# bluepill_voltage_reg_pcb.net
KiCad netlist of a schematic drawn in Altium Designer
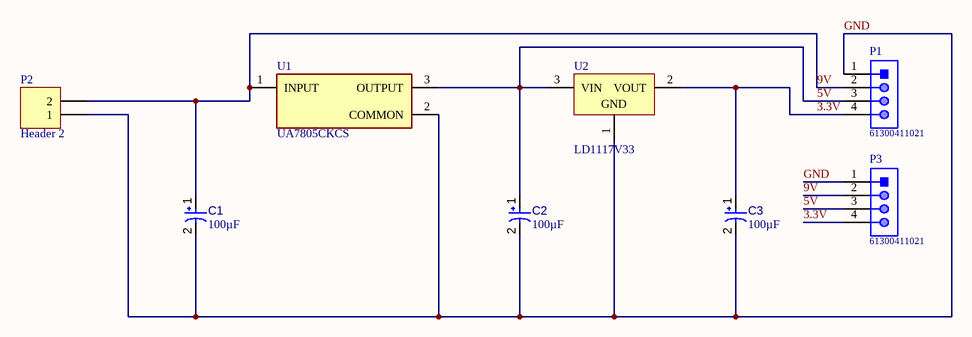
[diagram p0: bluepill_voltage_reg_pcb.SchDoc]

(export (version "E")
  (design (tool "Eeschema 10.0.6"))
  (components
    (comp (ref "C1")
      (value "100µF")
      (footprint "CAPPR65-500-1600X1000X1700")
      (description "Aluminum Electrolytic Capacitor, 100 uF, +/- 20%, 100 V, -40 to 85 degC, 2-Pin THD, RoHS, Bulk")
      (fields (field (name "MANUFACTURER") "Panasonic") (field (name "TOLERANCE") "20%"))
      (libsource (lib "UBC Rocket Aerostat") (part "CAP-P-2"))
    )
    (comp (ref "C2")
      (value "100µF")
      (footprint "CAPPR65-500-1600X1000X1700")
      (description "Aluminum Electrolytic Capacitor, 100 uF, +/- 20%, 100 V, -40 to 85 degC, 2-Pin THD, RoHS, Bulk")
      (fields (field (name "MANUFACTURER") "Panasonic") (field (name "TOLERANCE") "20%"))
      (libsource (lib "UBC Rocket Aerostat") (part "CAP-P-2"))
    )
    (comp (ref "C3")
      (value "100µF")
      (footprint "CAPPR65-500-1600X1000X1700")
      (description "Aluminum Electrolytic Capacitor, 100 uF, +/- 20%, 100 V, -40 to 85 degC, 2-Pin THD, RoHS, Bulk")
      (fields (field (name "MANUFACTURER") "Panasonic") (field (name "TOLERANCE") "20%"))
      (libsource (lib "UBC Rocket Aerostat") (part "CAP-P-2"))
    )
    (comp (ref "P1")
      (value "61300411021")
      (footprint "61300411021")
      (description "THT Angled Pin Header WR-PHD, Pitch 2.54 mm, Single Row, 4 pins")
      (fields (field (name "MANUFACTURER") "Wurth Elektronik") (field (name "PUBLISHER") "WurthElektronik"))
      (libsource (lib "Altium Content Vault") (part "WE-CN-1P-M-R4"))
    )
    (comp (ref "P2")
      (value "Header 2")
      (footprint "HDR1X2")
      (description "Header, 2-Pin")
      (fields (field (name "PUBLISHER") "Altium Limited"))
      (libsource (lib "Miscellaneous Connectors") (part "Header 2"))
    )
    (comp (ref "P3")
      (value "61300411021")
      (footprint "61300411021")
      (description "THT Angled Pin Header WR-PHD, Pitch 2.54 mm, Single Row, 4 pins")
      (fields (field (name "MANUFACTURER") "Wurth Elektronik") (field (name "PUBLISHER") "WurthElektronik"))
      (libsource (lib "Altium Content Vault") (part "WE-CN-1P-M-R4"))
    )
    (comp (ref "U1")
      (value "UA7805CKCS")
      (footprint "FP-KCS0003B-MFG")
      (description "Linear Voltage Regulator IC  1 Output  1.5A TO-220-3")
      (fields (field (name "MANUFACTURER") "Texas Instruments"))
      (libsource (lib "Altium Content Vault") (part "39cda3df25f6f2ed05b52b08d4ba2c1"))
    )
    (comp (ref "U2")
      (value "LD1117V33")
      (footprint "TO220")
      (description "Fixed Low Drop Positive Voltage Regulator, 3.3V, 3-Pin TO-220")
      (libsource (lib "Altium Content Vault") (part "PM-REG-LD1117V-SIL3"))
    )
  )
  (nets
    (net (code "1") (name "/3.3V") (class "Default")
      (node (ref "C3") (pin "1") (pinfunction "1_1") (pintype "passive"))
      (node (ref "P1") (pin "4") (pinfunction "4_4") (pintype "passive"))
      (node (ref "P3") (pin "4") (pinfunction "4_4") (pintype "passive"))
      (node (ref "U2") (pin "2") (pinfunction "VOUT_2") (pintype "power_in"))
    )
    (net (code "2") (name "/5V") (class "Default")
      (node (ref "C2") (pin "1") (pinfunction "1_1") (pintype "passive"))
      (node (ref "P1") (pin "3") (pinfunction "3_3") (pintype "passive"))
      (node (ref "P3") (pin "3") (pinfunction "3_3") (pintype "passive"))
      (node (ref "U1") (pin "3") (pinfunction "OUTPUT_3") (pintype "power_in"))
      (node (ref "U2") (pin "3") (pinfunction "VIN_3") (pintype "power_in"))
    )
    (net (code "3") (name "/9V") (class "Default")
      (node (ref "C1") (pin "1") (pinfunction "1_1") (pintype "passive"))
      (node (ref "P1") (pin "2") (pinfunction "2_2") (pintype "passive"))
      (node (ref "P2") (pin "2") (pinfunction "2_2") (pintype "passive"))
      (node (ref "P3") (pin "2") (pinfunction "2_2") (pintype "passive"))
      (node (ref "U1") (pin "1") (pinfunction "INPUT_1") (pintype "power_in"))
    )
    (net (code "4") (name "/GND") (class "Default")
      (node (ref "C1") (pin "2") (pinfunction "2_2") (pintype "passive"))
      (node (ref "C2") (pin "2") (pinfunction "2_2") (pintype "passive"))
      (node (ref "C3") (pin "2") (pinfunction "2_2") (pintype "passive"))
      (node (ref "P1") (pin "1") (pinfunction "1_1") (pintype "passive"))
      (node (ref "P2") (pin "1") (pinfunction "1_1") (pintype "passive"))
      (node (ref "P3") (pin "1") (pinfunction "1_1") (pintype "passive"))
      (node (ref "U1") (pin "2") (pinfunction "COMMON_2") (pintype "power_in"))
      (node (ref "U2") (pin "1") (pinfunction "GND_1") (pintype "power_in"))
    )
  )
)
